# WS2811Controller.net
KiCad netlist of a schematic drawn in EAGLE
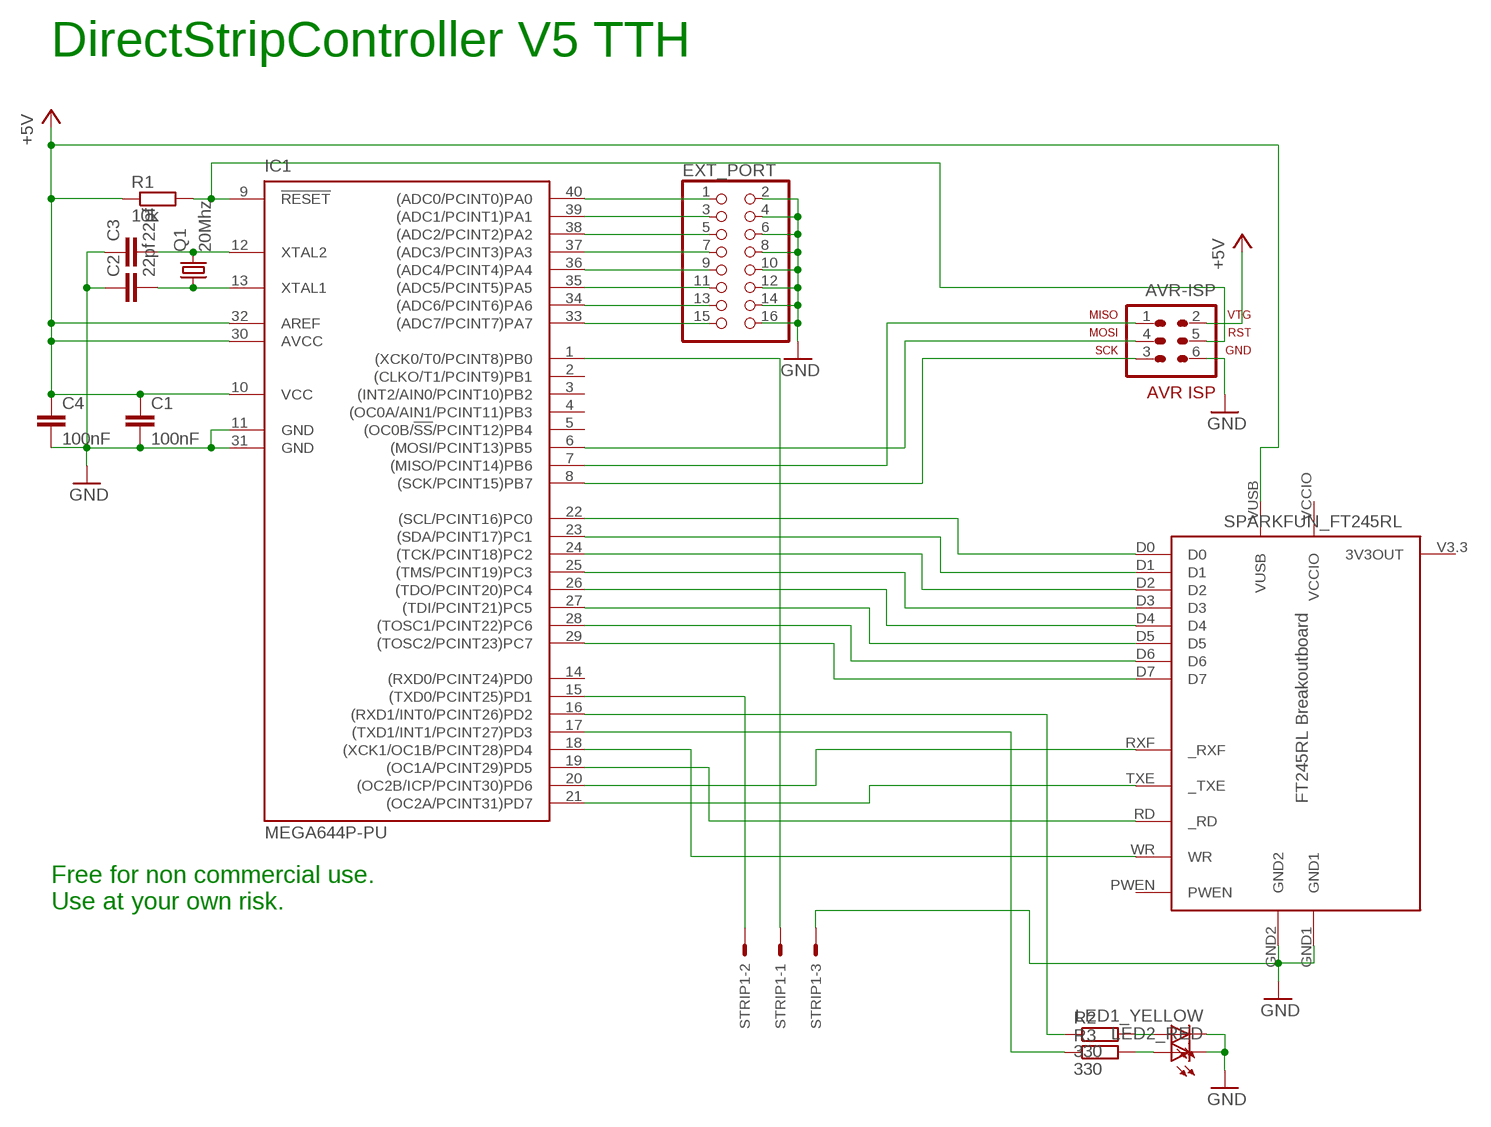
[diagram p0: schematic, sheet 1]

(export (version "E")
  (design (tool "Eeschema 10.0.6"))
  (components
    (comp (ref "AVR-ISP")
      (value "AVR-ISP-6")
      (footprint "eagle-import:AVR-ISP-6")
      (libsource (lib "eagle-import") (part "AVR-ISP-6"))
    )
    (comp (ref "C1")
      (value "100nF")
      (footprint "eagle-import:C025-025X050")
      (libsource (lib "eagle-import") (part "C-EU025-025X050"))
    )
    (comp (ref "C2")
      (value "22pf")
      (footprint "eagle-import:C025-025X050")
      (libsource (lib "eagle-import") (part "C-EU025-025X050"))
    )
    (comp (ref "C3")
      (value "22pf")
      (footprint "eagle-import:C025-025X050")
      (libsource (lib "eagle-import") (part "C-EU025-025X050"))
    )
    (comp (ref "C4")
      (value "100nF")
      (footprint "eagle-import:C025-025X050")
      (libsource (lib "eagle-import") (part "C-EU025-025X050"))
    )
    (comp (ref "EXT_PORT")
      (value "PINHD-2X8")
      (footprint "eagle-import:2X08")
      (libsource (lib "eagle-import") (part "PINHD-2X8"))
    )
    (comp (ref "IC1")
      (value "MEGA644P-PU")
      (footprint "eagle-import:DIL40")
      (libsource (lib "eagle-import") (part "MEGA164P/324P/644P-PU"))
    )
    (comp (ref "LED1_YELLOW")
      (value "LED3MM")
      (footprint "eagle-import:LED3MM")
      (libsource (lib "eagle-import") (part "LED3MM"))
    )
    (comp (ref "LED2_RED")
      (value "LED3MM")
      (footprint "eagle-import:LED3MM")
      (libsource (lib "eagle-import") (part "LED3MM"))
    )
    (comp (ref "Q1")
      (value "20Mhz")
      (footprint "eagle-import:HC49U-V")
      (libsource (lib "eagle-import") (part "CRYSTALHC49U-V"))
    )
    (comp (ref "R1")
      (value "10k")
      (footprint "eagle-import:0207_10")
      (libsource (lib "eagle-import") (part "R-EU_0207/10"))
    )
    (comp (ref "R2")
      (value "330")
      (footprint "eagle-import:0207_10")
      (libsource (lib "eagle-import") (part "R-EU_0207/10"))
    )
    (comp (ref "R3")
      (value "330")
      (footprint "eagle-import:0207_10")
      (libsource (lib "eagle-import") (part "R-EU_0207/10"))
    )
    (comp (ref "SPARKFUN_FT245RL")
      (value "FT245RL_BREAKOUTBOARD")
      (footprint "eagle-import:SPARKFUN_FT245RL_BOARD")
      (libsource (lib "eagle-import") (part "FT245RL_BREAKOUTBOARD"))
    )
    (comp (ref "STRIP1")
      (value "22-27-2031-03")
      (footprint "eagle-import:6410-03")
      (libsource (lib "eagle-import") (part "22-?-0327-2031"))
    )
  )
  (nets
    (net (code "1") (name "+5V") (class "Default")
      (node (ref "AVR-ISP") (pin "2") (pinfunction "2_2") (pintype "passive"))
      (node (ref "C1") (pin "1") (pinfunction "1_1") (pintype "passive"))
      (node (ref "C4") (pin "1") (pinfunction "1_1") (pintype "passive"))
      (node (ref "IC1") (pin "10") (pinfunction "VCC_10") (pintype "power_in"))
      (node (ref "IC1") (pin "30") (pinfunction "AVCC_30") (pintype "power_in"))
      (node (ref "IC1") (pin "32") (pinfunction "AREF_32") (pintype "power_in"))
      (node (ref "R1") (pin "1") (pinfunction "1_1") (pintype "passive"))
      (node (ref "SPARKFUN_FT245RL") (pin "VUSB") (pinfunction "VUSB_VUSB") (pintype "bidirectional"))
    )
    (net (code "2") (name "/VCCIO") (class "Default")
      (node (ref "SPARKFUN_FT245RL") (pin "VCCIO") (pinfunction "VCCIO_VCCIO") (pintype "power_in"))
    )
    (net (code "3") (name "GND") (class "Default")
      (node (ref "AVR-ISP") (pin "6") (pinfunction "6_6") (pintype "passive"))
      (node (ref "C1") (pin "2") (pinfunction "2_2") (pintype "passive"))
      (node (ref "C2") (pin "1") (pinfunction "1_1") (pintype "passive"))
      (node (ref "C3") (pin "1") (pinfunction "1_1") (pintype "passive"))
      (node (ref "C4") (pin "2") (pinfunction "2_2") (pintype "passive"))
      (node (ref "EXT_PORT") (pin "10") (pinfunction "10_10") (pintype "passive"))
      (node (ref "EXT_PORT") (pin "12") (pinfunction "12_12") (pintype "passive"))
      (node (ref "EXT_PORT") (pin "14") (pinfunction "14_14") (pintype "passive"))
      (node (ref "EXT_PORT") (pin "16") (pinfunction "16_16") (pintype "passive"))
      (node (ref "EXT_PORT") (pin "2") (pinfunction "2_2") (pintype "passive"))
      (node (ref "EXT_PORT") (pin "4") (pinfunction "4_4") (pintype "passive"))
      (node (ref "EXT_PORT") (pin "6") (pinfunction "6_6") (pintype "passive"))
      (node (ref "EXT_PORT") (pin "8") (pinfunction "8_8") (pintype "passive"))
      (node (ref "IC1") (pin "11") (pinfunction "GND_11") (pintype "power_in"))
      (node (ref "IC1") (pin "31") (pinfunction "GND_31") (pintype "power_in"))
      (node (ref "LED1_YELLOW") (pin "K") (pinfunction "C_K") (pintype "passive"))
      (node (ref "LED2_RED") (pin "K") (pinfunction "C_K") (pintype "passive"))
      (node (ref "SPARKFUN_FT245RL") (pin "GND1") (pinfunction "GND1_GND1") (pintype "power_in"))
      (node (ref "SPARKFUN_FT245RL") (pin "GND2") (pinfunction "GND2_GND2") (pintype "power_in"))
      (node (ref "STRIP1") (pin "3") (pinfunction "S_3") (pintype "passive"))
    )
    (net (code "4") (name "Net-(IC1-(ADC0{slash}PCINT0)PA0)") (class "Default")
      (node (ref "EXT_PORT") (pin "1") (pinfunction "1_1") (pintype "passive"))
      (node (ref "IC1") (pin "40") (pinfunction "(ADC0/PCINT0)PA0_40") (pintype "bidirectional"))
    )
    (net (code "5") (name "Net-(IC1-(ADC1{slash}PCINT1)PA1)") (class "Default")
      (node (ref "EXT_PORT") (pin "3") (pinfunction "3_3") (pintype "passive"))
      (node (ref "IC1") (pin "39") (pinfunction "(ADC1/PCINT1)PA1_39") (pintype "bidirectional"))
    )
    (net (code "6") (name "Net-(IC1-(ADC2{slash}PCINT2)PA2)") (class "Default")
      (node (ref "EXT_PORT") (pin "5") (pinfunction "5_5") (pintype "passive"))
      (node (ref "IC1") (pin "38") (pinfunction "(ADC2/PCINT2)PA2_38") (pintype "bidirectional"))
    )
    (net (code "7") (name "Net-(IC1-(ADC3{slash}PCINT3)PA3)") (class "Default")
      (node (ref "EXT_PORT") (pin "7") (pinfunction "7_7") (pintype "passive"))
      (node (ref "IC1") (pin "37") (pinfunction "(ADC3/PCINT3)PA3_37") (pintype "bidirectional"))
    )
    (net (code "8") (name "Net-(IC1-(ADC4{slash}PCINT4)PA4)") (class "Default")
      (node (ref "EXT_PORT") (pin "9") (pinfunction "9_9") (pintype "passive"))
      (node (ref "IC1") (pin "36") (pinfunction "(ADC4/PCINT4)PA4_36") (pintype "bidirectional"))
    )
    (net (code "9") (name "Net-(IC1-(ADC5{slash}PCINT5)PA5)") (class "Default")
      (node (ref "EXT_PORT") (pin "11") (pinfunction "11_11") (pintype "passive"))
      (node (ref "IC1") (pin "35") (pinfunction "(ADC5/PCINT5)PA5_35") (pintype "bidirectional"))
    )
    (net (code "10") (name "Net-(IC1-(ADC6{slash}PCINT6)PA6)") (class "Default")
      (node (ref "EXT_PORT") (pin "13") (pinfunction "13_13") (pintype "passive"))
      (node (ref "IC1") (pin "34") (pinfunction "(ADC6/PCINT6)PA6_34") (pintype "bidirectional"))
    )
    (net (code "11") (name "Net-(IC1-(ADC7{slash}PCINT7)PA7)") (class "Default")
      (node (ref "EXT_PORT") (pin "15") (pinfunction "15_15") (pintype "passive"))
      (node (ref "IC1") (pin "33") (pinfunction "(ADC7/PCINT7)PA7_33") (pintype "bidirectional"))
    )
    (net (code "12") (name "Net-(IC1-(MISO{slash}PCINT14)PB6)") (class "Default")
      (node (ref "AVR-ISP") (pin "1") (pinfunction "1_1") (pintype "passive"))
      (node (ref "IC1") (pin "7") (pinfunction "(MISO/PCINT14)PB6_7") (pintype "bidirectional"))
    )
    (net (code "13") (name "Net-(IC1-(MOSI{slash}PCINT13)PB5)") (class "Default")
      (node (ref "AVR-ISP") (pin "4") (pinfunction "4_4") (pintype "passive"))
      (node (ref "IC1") (pin "6") (pinfunction "(MOSI/PCINT13)PB5_6") (pintype "bidirectional"))
    )
    (net (code "14") (name "Net-(IC1-(OC1A{slash}PCINT29)PD5)") (class "Default")
      (node (ref "IC1") (pin "19") (pinfunction "(OC1A/PCINT29)PD5_19") (pintype "bidirectional"))
      (node (ref "SPARKFUN_FT245RL") (pin "RD") (pinfunction "_RD_RD") (pintype "bidirectional"))
    )
    (net (code "15") (name "Net-(IC1-(OC2A{slash}PCINT31)PD7)") (class "Default")
      (node (ref "IC1") (pin "21") (pinfunction "(OC2A/PCINT31)PD7_21") (pintype "bidirectional"))
      (node (ref "SPARKFUN_FT245RL") (pin "TXE") (pinfunction "_TXE_TXE") (pintype "bidirectional"))
    )
    (net (code "16") (name "Net-(IC1-(OC2B{slash}ICP{slash}PCINT30)PD6)") (class "Default")
      (node (ref "IC1") (pin "20") (pinfunction "(OC2B/ICP/PCINT30)PD6_20") (pintype "bidirectional"))
      (node (ref "SPARKFUN_FT245RL") (pin "RXF") (pinfunction "_RXF_RXF") (pintype "bidirectional"))
    )
    (net (code "17") (name "Net-(IC1-(RXD1{slash}INT0{slash}PCINT26)PD2)") (class "Default")
      (node (ref "IC1") (pin "16") (pinfunction "(RXD1/INT0/PCINT26)PD2_16") (pintype "bidirectional"))
      (node (ref "R2") (pin "1") (pinfunction "1_1") (pintype "passive"))
    )
    (net (code "18") (name "Net-(IC1-(SCK{slash}PCINT15)PB7)") (class "Default")
      (node (ref "AVR-ISP") (pin "3") (pinfunction "3_3") (pintype "passive"))
      (node (ref "IC1") (pin "8") (pinfunction "(SCK/PCINT15)PB7_8") (pintype "bidirectional"))
    )
    (net (code "19") (name "Net-(IC1-(SCL{slash}PCINT16)PC0)") (class "Default")
      (node (ref "IC1") (pin "22") (pinfunction "(SCL/PCINT16)PC0_22") (pintype "bidirectional"))
      (node (ref "SPARKFUN_FT245RL") (pin "D0") (pinfunction "D0_D0") (pintype "output"))
    )
    (net (code "20") (name "Net-(IC1-(SDA{slash}PCINT17)PC1)") (class "Default")
      (node (ref "IC1") (pin "23") (pinfunction "(SDA/PCINT17)PC1_23") (pintype "bidirectional"))
      (node (ref "SPARKFUN_FT245RL") (pin "D1") (pinfunction "D1_D1") (pintype "input"))
    )
    (net (code "21") (name "Net-(IC1-(TCK{slash}PCINT18)PC2)") (class "Default")
      (node (ref "IC1") (pin "24") (pinfunction "(TCK/PCINT18)PC2_24") (pintype "bidirectional"))
      (node (ref "SPARKFUN_FT245RL") (pin "D2") (pinfunction "D2_D2") (pintype "output"))
    )
    (net (code "22") (name "Net-(IC1-(TDI{slash}PCINT21)PC5)") (class "Default")
      (node (ref "IC1") (pin "27") (pinfunction "(TDI/PCINT21)PC5_27") (pintype "bidirectional"))
      (node (ref "SPARKFUN_FT245RL") (pin "D5") (pinfunction "D5_D5") (pintype "input"))
    )
    (net (code "23") (name "Net-(IC1-(TDO{slash}PCINT20)PC4)") (class "Default")
      (node (ref "IC1") (pin "26") (pinfunction "(TDO/PCINT20)PC4_26") (pintype "bidirectional"))
      (node (ref "SPARKFUN_FT245RL") (pin "D4") (pinfunction "D4_D4") (pintype "output"))
    )
    (net (code "24") (name "Net-(IC1-(TMS{slash}PCINT19)PC3)") (class "Default")
      (node (ref "IC1") (pin "25") (pinfunction "(TMS/PCINT19)PC3_25") (pintype "bidirectional"))
      (node (ref "SPARKFUN_FT245RL") (pin "D3") (pinfunction "D3_D3") (pintype "input"))
    )
    (net (code "25") (name "Net-(IC1-(TOSC1{slash}PCINT22)PC6)") (class "Default")
      (node (ref "IC1") (pin "28") (pinfunction "(TOSC1/PCINT22)PC6_28") (pintype "bidirectional"))
      (node (ref "SPARKFUN_FT245RL") (pin "D6") (pinfunction "D6_D6") (pintype "input"))
    )
    (net (code "26") (name "Net-(IC1-(TOSC2{slash}PCINT23)PC7)") (class "Default")
      (node (ref "IC1") (pin "29") (pinfunction "(TOSC2/PCINT23)PC7_29") (pintype "bidirectional"))
      (node (ref "SPARKFUN_FT245RL") (pin "D7") (pinfunction "D7_D7") (pintype "input"))
    )
    (net (code "27") (name "Net-(IC1-(TXD0{slash}PCINT25)PD1)") (class "Default")
      (node (ref "IC1") (pin "15") (pinfunction "(TXD0/PCINT25)PD1_15") (pintype "bidirectional"))
      (node (ref "STRIP1") (pin "2") (pinfunction "S_2") (pintype "passive"))
    )
    (net (code "28") (name "Net-(IC1-(TXD1{slash}INT1{slash}PCINT27)PD3)") (class "Default")
      (node (ref "IC1") (pin "17") (pinfunction "(TXD1/INT1/PCINT27)PD3_17") (pintype "bidirectional"))
      (node (ref "R3") (pin "1") (pinfunction "1_1") (pintype "passive"))
    )
    (net (code "29") (name "Net-(IC1-(XCK0{slash}T0{slash}PCINT8)PB0)") (class "Default")
      (node (ref "IC1") (pin "1") (pinfunction "(XCK0/T0/PCINT8)PB0_1") (pintype "bidirectional"))
      (node (ref "STRIP1") (pin "1") (pinfunction "S_1") (pintype "passive"))
    )
    (net (code "30") (name "Net-(IC1-(XCK1{slash}OC1B{slash}PCINT28)PD4)") (class "Default")
      (node (ref "IC1") (pin "18") (pinfunction "(XCK1/OC1B/PCINT28)PD4_18") (pintype "bidirectional"))
      (node (ref "SPARKFUN_FT245RL") (pin "WR") (pinfunction "WR_WR") (pintype "bidirectional"))
    )
    (net (code "31") (name "Net-(IC1-XTAL1)") (class "Default")
      (node (ref "C2") (pin "2") (pinfunction "2_2") (pintype "passive"))
      (node (ref "IC1") (pin "13") (pinfunction "XTAL1_13") (pintype "input"))
      (node (ref "Q1") (pin "1") (pinfunction "1_1") (pintype "passive"))
    )
    (net (code "32") (name "Net-(IC1-XTAL2)") (class "Default")
      (node (ref "C3") (pin "2") (pinfunction "2_2") (pintype "passive"))
      (node (ref "IC1") (pin "12") (pinfunction "XTAL2_12") (pintype "output"))
      (node (ref "Q1") (pin "2") (pinfunction "2_2") (pintype "passive"))
    )
    (net (code "33") (name "Net-(IC1-~{RESET})") (class "Default")
      (node (ref "AVR-ISP") (pin "5") (pinfunction "5_5") (pintype "passive"))
      (node (ref "IC1") (pin "9") (pinfunction "~{RESET}_9") (pintype "input"))
      (node (ref "R1") (pin "2") (pinfunction "2_2") (pintype "passive"))
    )
    (net (code "34") (name "Net-(LED1_YELLOW-PadA)") (class "Default")
      (node (ref "LED1_YELLOW") (pin "A") (pinfunction "A_A") (pintype "passive"))
      (node (ref "R2") (pin "2") (pinfunction "2_2") (pintype "passive"))
    )
    (net (code "35") (name "Net-(LED2_RED-PadA)") (class "Default")
      (node (ref "LED2_RED") (pin "A") (pinfunction "A_A") (pintype "passive"))
      (node (ref "R3") (pin "2") (pinfunction "2_2") (pintype "passive"))
    )
    (net (code "36") (name "unconnected-(IC1-(CLKO{slash}T1{slash}PCINT9)PB1-Pad2)") (class "Default")
      (node (ref "IC1") (pin "2") (pinfunction "(CLKO/T1/PCINT9)PB1_2") (pintype "bidirectional"))
    )
    (net (code "37") (name "unconnected-(IC1-(INT2{slash}AIN0{slash}PCINT10)PB2-Pad3)") (class "Default")
      (node (ref "IC1") (pin "3") (pinfunction "(INT2/AIN0/PCINT10)PB2_3") (pintype "bidirectional"))
    )
    (net (code "38") (name "unconnected-(IC1-(OC0A{slash}AIN1{slash}PCINT11)PB3-Pad4)") (class "Default")
      (node (ref "IC1") (pin "4") (pinfunction "(OC0A/AIN1/PCINT11)PB3_4") (pintype "bidirectional"))
    )
    (net (code "39") (name "unconnected-(IC1-(OC0B{slash}~{SS}{slash}PCINT12)PB4-Pad5)") (class "Default")
      (node (ref "IC1") (pin "5") (pinfunction "(OC0B/~{SS}/PCINT12)PB4_5") (pintype "bidirectional"))
    )
    (net (code "40") (name "unconnected-(IC1-(RXD0{slash}PCINT24)PD0-Pad14)") (class "Default")
      (node (ref "IC1") (pin "14") (pinfunction "(RXD0/PCINT24)PD0_14") (pintype "bidirectional"))
    )
    (net (code "41") (name "unconnected-(SPARKFUN_FT245RL-3V3OUT-PadV3.3)") (class "Default")
      (node (ref "SPARKFUN_FT245RL") (pin "V3.3") (pinfunction "3V3OUT_V3.3") (pintype "output"))
    )
    (net (code "42") (name "unconnected-(SPARKFUN_FT245RL-PadPWEN)") (class "Default")
      (node (ref "SPARKFUN_FT245RL") (pin "PWEN") (pinfunction "PWEN_PWEN") (pintype "bidirectional"))
    )
  )
)
